# Aquarium_Temperatur.net
KiCad netlist of a schematic drawn in EasyEDA
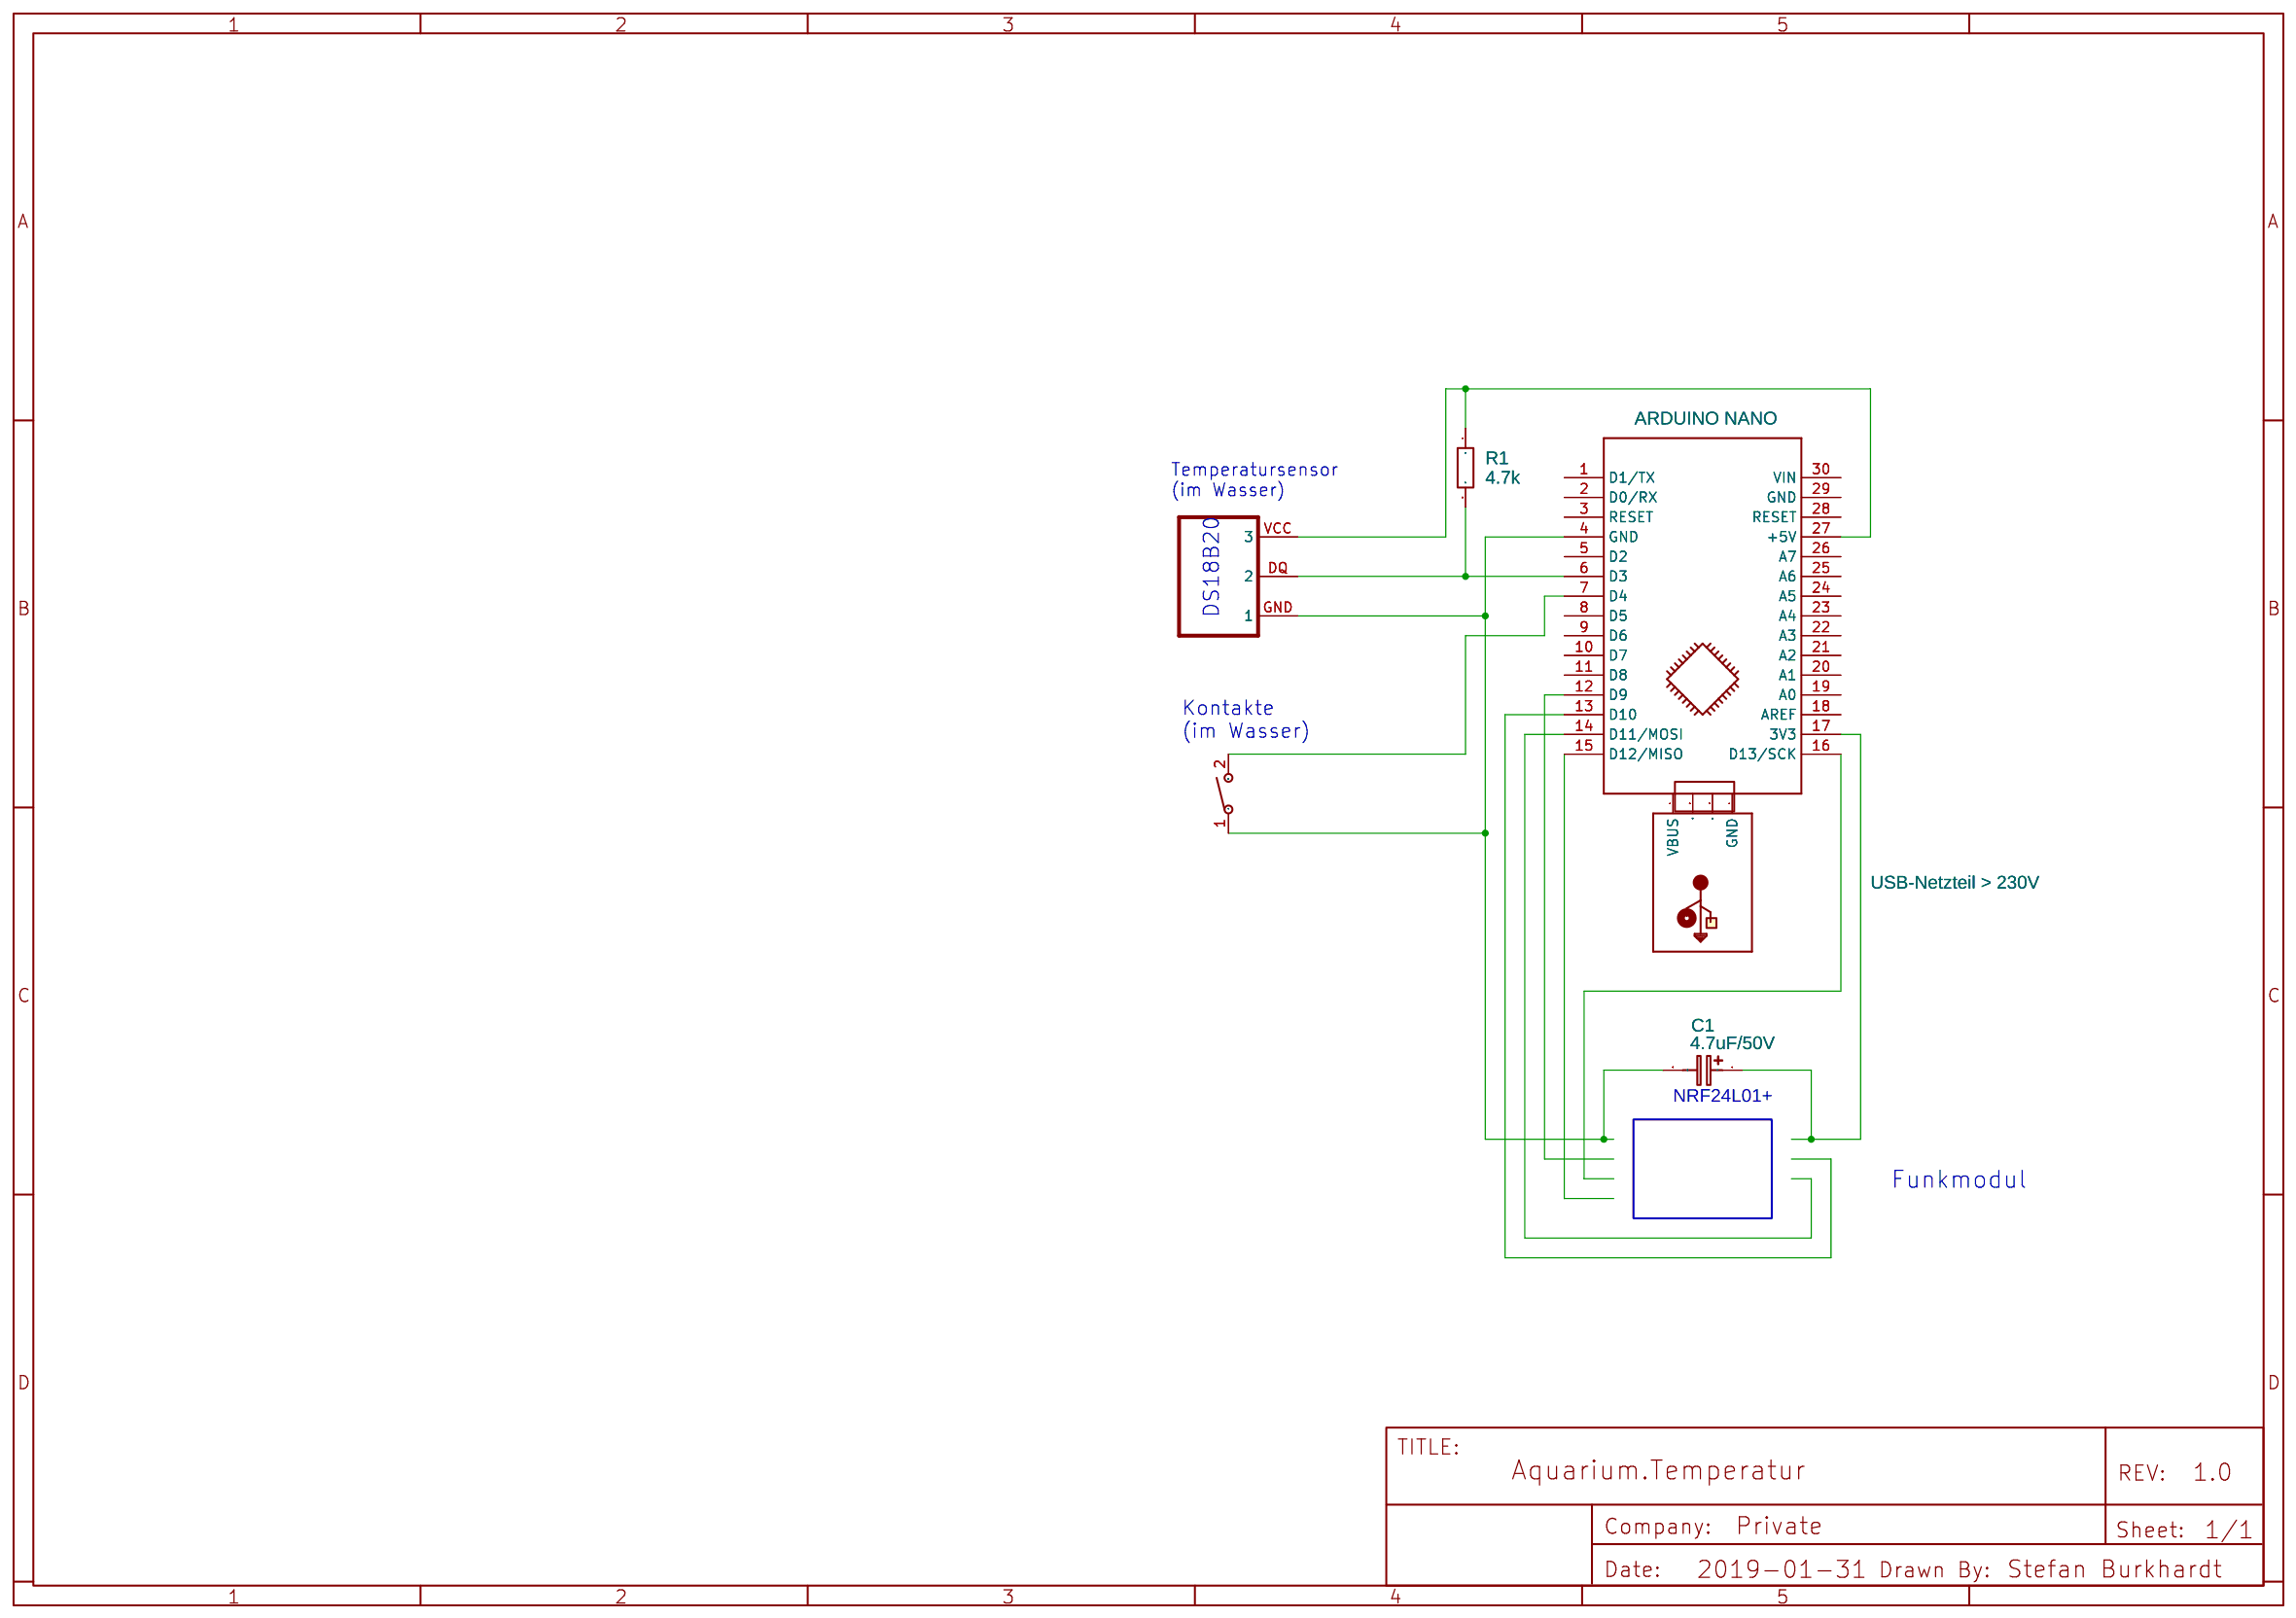
[diagram p0: schematic sheet]

(export (version "E")
  (design (tool "Eeschema 10.0.6"))
  (components
    (comp (ref "C1")
      (value "4.7uF/50V")
      (fields (field (name "BOM_Manufacturer Part") "?"))
      (libsource (lib "") (part "Cap_Electrolytic(TH)_D3.0XF1.5_EU"))
    )
    (comp (ref "R1")
      (value "4.7k")
      (fields (field (name "BOM_Manufacturer Part") "?"))
      (libsource (lib "") (part "Res_AXIAL-0.3(1/8W)_EU"))
    )
    (comp (ref "SW1")
      (value "Wasser-Kurzschluss")
      (fields
        (field (name "BOM_Manufacturer Part") "K2-1107ST-A4SW-06")
        (field (name "BOM_Supplier Part") "C118141")
      )
      (libsource (lib "") (part "Unknown_615_395"))
    )
    (comp (ref "U1")
      (value "ARDUINO NANO")
      (fields (field (name "BOM_Manufacturer Part") "?"))
      (libsource (lib "") (part "Unknown_855_310"))
    )
    (comp (ref "U2")
      (value "DS18B20")
      (fields (field (name "BOM_Manufacturer Part") "?"))
      (libsource (lib "") (part "Unknown_650_305"))
    )
    (comp (ref "X1")
      (value "USB-Netzteil > 230V")
      (fields (field (name "BOM_Manufacturer Part") "?"))
      (libsource (lib "") (part "Unknown_855_435"))
    )
  )
  (nets
    (net (code "1") (name "Net-(U1-+5V)") (class "Default")
      (node (ref "R1") (pin "1") (pinfunction "1_1") (pintype "unspecified"))
      (node (ref "U1") (pin "27") (pinfunction "+5V_27") (pintype "unspecified"))
      (node (ref "U2") (pin "VCC") (pinfunction "3_VCC") (pintype "unspecified"))
    )
    (net (code "2") (name "Net-(U1-3V3)") (class "Default")
      (node (ref "C1") (pin "1") (pinfunction "1_1") (pintype "unspecified"))
      (node (ref "U1") (pin "17") (pinfunction "3V3_17") (pintype "unspecified"))
    )
    (net (code "3") (name "Net-(U1-D3)") (class "Default")
      (node (ref "R1") (pin "2") (pinfunction "2_2") (pintype "unspecified"))
      (node (ref "U1") (pin "6") (pinfunction "D3_6") (pintype "unspecified"))
      (node (ref "U2") (pin "DQ") (pinfunction "2_DQ") (pintype "unspecified"))
    )
    (net (code "4") (name "Net-(U1-D4)") (class "Default")
      (node (ref "SW1") (pin "2") (pinfunction "2_2") (pintype "unspecified"))
      (node (ref "U1") (pin "7") (pinfunction "D4_7") (pintype "unspecified"))
    )
    (net (code "5") (name "Net-(U2-1)") (class "Default")
      (node (ref "C1") (pin "2") (pinfunction "2_2") (pintype "unspecified"))
      (node (ref "SW1") (pin "1") (pinfunction "1_1") (pintype "unspecified"))
      (node (ref "U1") (pin "4") (pinfunction "GND_4") (pintype "unspecified"))
      (node (ref "U2") (pin "GND") (pinfunction "1_GND") (pintype "unspecified"))
    )
    (net (code "6") (name "unconnected-(U1-A0-Pad19)") (class "Default")
      (node (ref "U1") (pin "19") (pinfunction "A0_19") (pintype "unspecified"))
    )
    (net (code "7") (name "unconnected-(U1-A1-Pad20)") (class "Default")
      (node (ref "U1") (pin "20") (pinfunction "A1_20") (pintype "unspecified"))
    )
    (net (code "8") (name "unconnected-(U1-A2-Pad21)") (class "Default")
      (node (ref "U1") (pin "21") (pinfunction "A2_21") (pintype "unspecified"))
    )
    (net (code "9") (name "unconnected-(U1-A3-Pad22)") (class "Default")
      (node (ref "U1") (pin "22") (pinfunction "A3_22") (pintype "unspecified"))
    )
    (net (code "10") (name "unconnected-(U1-A4-Pad23)") (class "Default")
      (node (ref "U1") (pin "23") (pinfunction "A4_23") (pintype "unspecified"))
    )
    (net (code "11") (name "unconnected-(U1-A5-Pad24)") (class "Default")
      (node (ref "U1") (pin "24") (pinfunction "A5_24") (pintype "unspecified"))
    )
    (net (code "12") (name "unconnected-(U1-A6-Pad25)") (class "Default")
      (node (ref "U1") (pin "25") (pinfunction "A6_25") (pintype "unspecified"))
    )
    (net (code "13") (name "unconnected-(U1-A7-Pad26)") (class "Default")
      (node (ref "U1") (pin "26") (pinfunction "A7_26") (pintype "unspecified"))
    )
    (net (code "14") (name "unconnected-(U1-AREF-Pad18)") (class "Default")
      (node (ref "U1") (pin "18") (pinfunction "AREF_18") (pintype "unspecified"))
    )
    (net (code "15") (name "unconnected-(U1-D0{slash}RX-Pad2)") (class "Default")
      (node (ref "U1") (pin "2") (pinfunction "D0/RX_2") (pintype "unspecified"))
    )
    (net (code "16") (name "unconnected-(U1-D1{slash}TX-Pad1)") (class "Default")
      (node (ref "U1") (pin "1") (pinfunction "D1/TX_1") (pintype "unspecified"))
    )
    (net (code "17") (name "unconnected-(U1-D2-Pad5)") (class "Default")
      (node (ref "U1") (pin "5") (pinfunction "D2_5") (pintype "unspecified"))
    )
    (net (code "18") (name "unconnected-(U1-D5-Pad8)") (class "Default")
      (node (ref "U1") (pin "8") (pinfunction "D5_8") (pintype "unspecified"))
    )
    (net (code "19") (name "unconnected-(U1-D6-Pad9)") (class "Default")
      (node (ref "U1") (pin "9") (pinfunction "D6_9") (pintype "unspecified"))
    )
    (net (code "20") (name "unconnected-(U1-D7-Pad10)") (class "Default")
      (node (ref "U1") (pin "10") (pinfunction "D7_10") (pintype "unspecified"))
    )
    (net (code "21") (name "unconnected-(U1-D8-Pad11)") (class "Default")
      (node (ref "U1") (pin "11") (pinfunction "D8_11") (pintype "unspecified"))
    )
    (net (code "22") (name "unconnected-(U1-D9-Pad12)") (class "Default")
      (node (ref "U1") (pin "12") (pinfunction "D9_12") (pintype "unspecified"))
    )
    (net (code "23") (name "unconnected-(U1-D10-Pad13)") (class "Default")
      (node (ref "U1") (pin "13") (pinfunction "D10_13") (pintype "unspecified"))
    )
    (net (code "24") (name "unconnected-(U1-D11{slash}MOSI-Pad14)") (class "Default")
      (node (ref "U1") (pin "14") (pinfunction "D11/MOSI_14") (pintype "unspecified"))
    )
    (net (code "25") (name "unconnected-(U1-D12{slash}MISO-Pad15)") (class "Default")
      (node (ref "U1") (pin "15") (pinfunction "D12/MISO_15") (pintype "unspecified"))
    )
    (net (code "26") (name "unconnected-(U1-D13{slash}SCK-Pad16)") (class "Default")
      (node (ref "U1") (pin "16") (pinfunction "D13/SCK_16") (pintype "unspecified"))
    )
    (net (code "27") (name "unconnected-(U1-GND-Pad29)") (class "Default")
      (node (ref "U1") (pin "29") (pinfunction "GND_29") (pintype "unspecified"))
    )
    (net (code "28") (name "unconnected-(U1-RESET-Pad3)") (class "Default")
      (node (ref "U1") (pin "3") (pinfunction "RESET_3") (pintype "unspecified"))
    )
    (net (code "29") (name "unconnected-(U1-RESET-Pad28)") (class "Default")
      (node (ref "U1") (pin "28") (pinfunction "RESET_28") (pintype "unspecified"))
    )
    (net (code "30") (name "unconnected-(U1-VIN-Pad30)") (class "Default")
      (node (ref "U1") (pin "30") (pinfunction "VIN_30") (pintype "unspecified"))
    )
    (net (code "31") (name "unconnected-(X1-D+-Pad3)") (class "Default")
      (node (ref "X1") (pin "3") (pinfunction "D+_3") (pintype "unspecified"))
    )
    (net (code "32") (name "unconnected-(X1-D--Pad2)") (class "Default")
      (node (ref "X1") (pin "2") (pinfunction "D-_2") (pintype "unspecified"))
    )
    (net (code "33") (name "unconnected-(X1-GND-Pad4)") (class "Default")
      (node (ref "X1") (pin "4") (pinfunction "GND_4") (pintype "passive"))
    )
    (net (code "34") (name "unconnected-(X1-VBUS-Pad1)") (class "Default")
      (node (ref "X1") (pin "1") (pinfunction "VBUS_1") (pintype "passive"))
    )
  )
)
